# MS20vcf.net
KiCad netlist of a schematic drawn in EAGLE
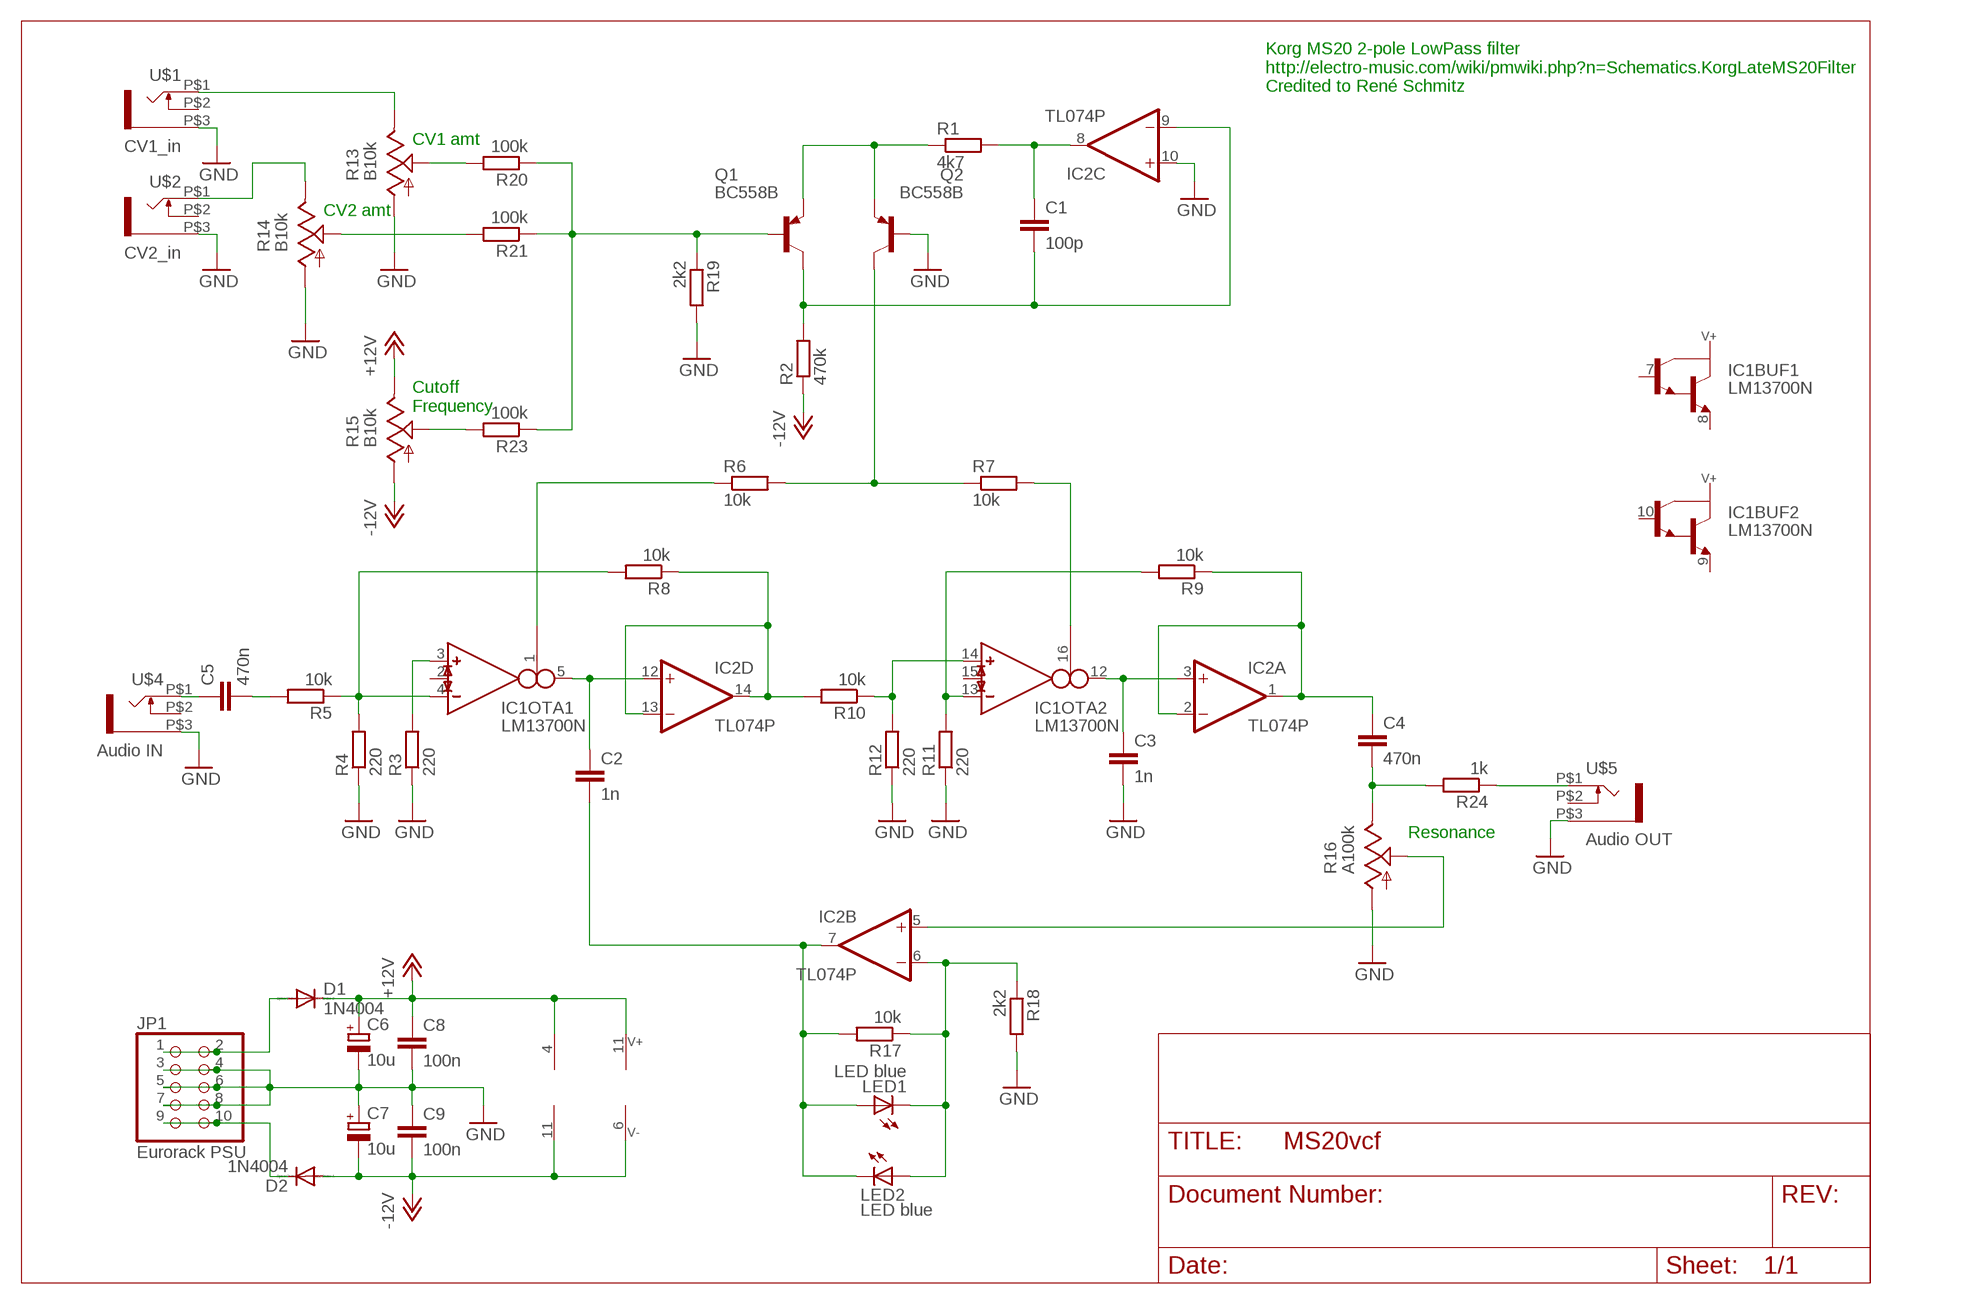
[diagram p0: schematic, sheet 1]

(export (version "E")
  (design (tool "Eeschema 10.0.6"))
  (components
    (comp (ref "C1")
      (value "100p")
      (footprint "eagle-import:C025-025X050")
      (libsource (lib "eagle-import") (part "C-EU025-025X050"))
    )
    (comp (ref "C2")
      (value "1n")
      (footprint "eagle-import:C050-025X075")
      (libsource (lib "eagle-import") (part "C-EU050-025X075"))
    )
    (comp (ref "C3")
      (value "1n")
      (footprint "eagle-import:C050-025X075")
      (libsource (lib "eagle-import") (part "C-EU050-025X075"))
    )
    (comp (ref "C4")
      (value "470n")
      (footprint "eagle-import:C050-025X075")
      (libsource (lib "eagle-import") (part "C-EU050-025X075"))
    )
    (comp (ref "C5")
      (value "470n")
      (footprint "eagle-import:C050-025X075")
      (libsource (lib "eagle-import") (part "C-EU050-025X075"))
    )
    (comp (ref "C6")
      (value "10u")
      (footprint "eagle-import:E2,5-5")
      (libsource (lib "eagle-import") (part "CPOL-EUE2.5-5"))
    )
    (comp (ref "C7")
      (value "10u")
      (footprint "eagle-import:E2,5-5")
      (libsource (lib "eagle-import") (part "CPOL-EUE2.5-5"))
    )
    (comp (ref "C8")
      (value "100n")
      (footprint "eagle-import:C025-025X050")
      (libsource (lib "eagle-import") (part "C-EU025-025X050"))
    )
    (comp (ref "C9")
      (value "100n")
      (footprint "eagle-import:C025-025X050")
      (libsource (lib "eagle-import") (part "C-EU025-025X050"))
    )
    (comp (ref "D1")
      (value "1N4004")
      (footprint "eagle-import:D-7.5")
      (libsource (lib "eagle-import") (part "DIODE-D-7.5"))
    )
    (comp (ref "D2")
      (value "1N4004")
      (footprint "eagle-import:D-7.5")
      (libsource (lib "eagle-import") (part "DIODE-D-7.5"))
    )
    (comp (ref "IC1")
      (value "LM13700N")
      (footprint "eagle-import:DIL16")
      (libsource (lib "eagle-import") (part "LM13700N"))
    )
    (comp (ref "IC2")
      (value "TL074P")
      (footprint "eagle-import:DIL14")
      (libsource (lib "eagle-import") (part "TL074P"))
    )
    (comp (ref "JP1")
      (value "Eurorack PSU")
      (footprint "eagle-import:2X05")
      (libsource (lib "eagle-import") (part "PINHD-2X5"))
    )
    (comp (ref "LED1")
      (value "LED blue")
      (footprint "eagle-import:LED3MM")
      (libsource (lib "eagle-import") (part "LED3MM"))
    )
    (comp (ref "LED2")
      (value "LED blue")
      (footprint "eagle-import:LED3MM")
      (libsource (lib "eagle-import") (part "LED3MM"))
    )
    (comp (ref "Q1")
      (value "BC558B")
      (footprint "eagle-import:TO92-EBC")
      (libsource (lib "eagle-import") (part "BC558C"))
    )
    (comp (ref "Q2")
      (value "BC558B")
      (footprint "eagle-import:TO92-EBC")
      (libsource (lib "eagle-import") (part "BC558C"))
    )
    (comp (ref "R1")
      (value "4k7")
      (footprint "eagle-import:0207_2V")
      (libsource (lib "eagle-import") (part "R-EU_0207/2V"))
    )
    (comp (ref "R2")
      (value "470k")
      (footprint "eagle-import:0207_2V")
      (libsource (lib "eagle-import") (part "R-EU_0207/2V"))
    )
    (comp (ref "R3")
      (value "220")
      (footprint "eagle-import:0207_2V")
      (libsource (lib "eagle-import") (part "R-EU_0207/2V"))
    )
    (comp (ref "R4")
      (value "220")
      (footprint "eagle-import:0207_2V")
      (libsource (lib "eagle-import") (part "R-EU_0207/2V"))
    )
    (comp (ref "R5")
      (value "10k")
      (footprint "eagle-import:0207_2V")
      (libsource (lib "eagle-import") (part "R-EU_0207/2V"))
    )
    (comp (ref "R6")
      (value "10k")
      (footprint "eagle-import:0207_2V")
      (libsource (lib "eagle-import") (part "R-EU_0207/2V"))
    )
    (comp (ref "R7")
      (value "10k")
      (footprint "eagle-import:0207_2V")
      (libsource (lib "eagle-import") (part "R-EU_0207/2V"))
    )
    (comp (ref "R8")
      (value "10k")
      (footprint "eagle-import:0207_2V")
      (libsource (lib "eagle-import") (part "R-EU_0207/2V"))
    )
    (comp (ref "R9")
      (value "10k")
      (footprint "eagle-import:0207_2V")
      (libsource (lib "eagle-import") (part "R-EU_0207/2V"))
    )
    (comp (ref "R10")
      (value "10k")
      (footprint "eagle-import:0207_2V")
      (libsource (lib "eagle-import") (part "R-EU_0207/2V"))
    )
    (comp (ref "R11")
      (value "220")
      (footprint "eagle-import:0207_2V")
      (libsource (lib "eagle-import") (part "R-EU_0207/2V"))
    )
    (comp (ref "R12")
      (value "220")
      (footprint "eagle-import:0207_2V")
      (libsource (lib "eagle-import") (part "R-EU_0207/2V"))
    )
    (comp (ref "R13")
      (value "B10k")
      (footprint "eagle-import:ALPS_POT_VERTICAL")
      (libsource (lib "eagle-import") (part "POT_USVERTICAL"))
    )
    (comp (ref "R14")
      (value "B10k")
      (footprint "eagle-import:ALPS_POT_VERTICAL")
      (libsource (lib "eagle-import") (part "POT_USVERTICAL"))
    )
    (comp (ref "R15")
      (value "B10k")
      (footprint "eagle-import:ALPS_POT_VERTICAL")
      (libsource (lib "eagle-import") (part "POT_USVERTICAL"))
    )
    (comp (ref "R16")
      (value "A100k")
      (footprint "eagle-import:ALPS_POT_VERTICAL")
      (libsource (lib "eagle-import") (part "POT_USVERTICAL"))
    )
    (comp (ref "R17")
      (value "10k")
      (footprint "eagle-import:0207_2V")
      (libsource (lib "eagle-import") (part "R-EU_0207/2V"))
    )
    (comp (ref "R18")
      (value "2k2")
      (footprint "eagle-import:0207_2V")
      (libsource (lib "eagle-import") (part "R-EU_0207/2V"))
    )
    (comp (ref "R19")
      (value "2k2")
      (footprint "eagle-import:0207_2V")
      (libsource (lib "eagle-import") (part "R-EU_0207/2V"))
    )
    (comp (ref "R20")
      (value "100k")
      (footprint "eagle-import:0207_2V")
      (libsource (lib "eagle-import") (part "R-EU_0207/2V"))
    )
    (comp (ref "R21")
      (value "100k")
      (footprint "eagle-import:0207_2V")
      (libsource (lib "eagle-import") (part "R-EU_0207/2V"))
    )
    (comp (ref "R23")
      (value "100k")
      (footprint "eagle-import:0207_2V")
      (libsource (lib "eagle-import") (part "R-EU_0207/2V"))
    )
    (comp (ref "R24")
      (value "1k")
      (footprint "eagle-import:0207_2V")
      (libsource (lib "eagle-import") (part "R-EU_0207/2V"))
    )
    (comp (ref "U$1")
      (value "CV1_in")
      (footprint "eagle-import:WQP-PJ301M-12_JACK")
      (libsource (lib "eagle-import") (part "WQP-PJ301M-12_JACK"))
    )
    (comp (ref "U$2")
      (value "CV2_in")
      (footprint "eagle-import:WQP-PJ301M-12_JACK")
      (libsource (lib "eagle-import") (part "WQP-PJ301M-12_JACK"))
    )
    (comp (ref "U$4")
      (value "Audio IN")
      (footprint "eagle-import:WQP-PJ301M-12_JACK")
      (libsource (lib "eagle-import") (part "WQP-PJ301M-12_JACK"))
    )
    (comp (ref "U$5")
      (value "Audio OUT")
      (footprint "eagle-import:WQP-PJ301M-12_JACK")
      (libsource (lib "eagle-import") (part "WQP-PJ301M-12_JACK"))
    )
  )
  (nets
    (net (code "1") (name "+12V") (class "Default")
      (node (ref "C6") (pin "+") (pinfunction "+_+") (pintype "passive"))
      (node (ref "C8") (pin "1") (pinfunction "1_1") (pintype "passive"))
      (node (ref "D1") (pin "C") (pinfunction "C_C") (pintype "passive"))
      (node (ref "IC1") (pin "11") (pinfunction "V+_11") (pintype "power_in"))
      (node (ref "IC2") (pin "4") (pinfunction "V+_4") (pintype "power_in"))
      (node (ref "R15") (pin "P$1") (pinfunction "E_P$1") (pintype "passive"))
    )
    (net (code "2") (name "-12V") (class "Default")
      (node (ref "C7") (pin "-") (pinfunction "-_-") (pintype "passive"))
      (node (ref "C9") (pin "2") (pinfunction "2_2") (pintype "passive"))
      (node (ref "D2") (pin "A") (pinfunction "A_A") (pintype "passive"))
      (node (ref "IC1") (pin "6") (pinfunction "V-_6") (pintype "power_in"))
      (node (ref "IC2") (pin "11") (pinfunction "V-_11") (pintype "power_in"))
      (node (ref "R15") (pin "P$3") (pinfunction "A_P$3") (pintype "passive"))
      (node (ref "R2") (pin "1") (pinfunction "1_1") (pintype "passive"))
    )
    (net (code "3") (name "GND") (class "Default")
      (node (ref "C3") (pin "2") (pinfunction "2_2") (pintype "passive"))
      (node (ref "C6") (pin "-") (pinfunction "-_-") (pintype "passive"))
      (node (ref "C7") (pin "+") (pinfunction "+_+") (pintype "passive"))
      (node (ref "C8") (pin "2") (pinfunction "2_2") (pintype "passive"))
      (node (ref "C9") (pin "1") (pinfunction "1_1") (pintype "passive"))
      (node (ref "IC2") (pin "10") (pinfunction "+IN_10") (pintype "input"))
      (node (ref "JP1") (pin "3") (pinfunction "3_3") (pintype "passive"))
      (node (ref "JP1") (pin "4") (pinfunction "4_4") (pintype "passive"))
      (node (ref "JP1") (pin "5") (pinfunction "5_5") (pintype "passive"))
      (node (ref "JP1") (pin "6") (pinfunction "6_6") (pintype "passive"))
      (node (ref "JP1") (pin "7") (pinfunction "7_7") (pintype "passive"))
      (node (ref "JP1") (pin "8") (pinfunction "8_8") (pintype "passive"))
      (node (ref "Q2") (pin "B") (pinfunction "B_B") (pintype "passive"))
      (node (ref "R11") (pin "1") (pinfunction "1_1") (pintype "passive"))
      (node (ref "R12") (pin "1") (pinfunction "1_1") (pintype "passive"))
      (node (ref "R13") (pin "P$3") (pinfunction "A_P$3") (pintype "passive"))
      (node (ref "R14") (pin "P$3") (pinfunction "A_P$3") (pintype "passive"))
      (node (ref "R16") (pin "P$3") (pinfunction "A_P$3") (pintype "passive"))
      (node (ref "R18") (pin "2") (pinfunction "2_2") (pintype "passive"))
      (node (ref "R19") (pin "2") (pinfunction "2_2") (pintype "passive"))
      (node (ref "R3") (pin "1") (pinfunction "1_1") (pintype "passive"))
      (node (ref "R4") (pin "1") (pinfunction "1_1") (pintype "passive"))
      (node (ref "U$1") (pin "P$3") (pinfunction "1_P$3") (pintype "passive"))
      (node (ref "U$2") (pin "P$3") (pinfunction "1_P$3") (pintype "passive"))
      (node (ref "U$4") (pin "P$3") (pinfunction "1_P$3") (pintype "passive"))
      (node (ref "U$5") (pin "P$3") (pinfunction "1_P$3") (pintype "passive"))
    )
    (net (code "4") (name "Net-(C5-Pad2)") (class "Default")
      (node (ref "C5") (pin "2") (pinfunction "2_2") (pintype "passive"))
      (node (ref "R5") (pin "2") (pinfunction "2_2") (pintype "passive"))
    )
    (net (code "5") (name "Net-(D1-PadA)") (class "Default")
      (node (ref "D1") (pin "A") (pinfunction "A_A") (pintype "passive"))
      (node (ref "JP1") (pin "1") (pinfunction "1_1") (pintype "passive"))
      (node (ref "JP1") (pin "2") (pinfunction "2_2") (pintype "passive"))
    )
    (net (code "6") (name "Net-(D2-PadC)") (class "Default")
      (node (ref "D2") (pin "C") (pinfunction "C_C") (pintype "passive"))
      (node (ref "JP1") (pin "10") (pinfunction "10_10") (pintype "passive"))
      (node (ref "JP1") (pin "9") (pinfunction "9_9") (pintype "passive"))
    )
    (net (code "7") (name "Net-(IC1C-IN_N)") (class "Default")
      (node (ref "IC1") (pin "4") (pinfunction "IN_N_4") (pintype "input"))
      (node (ref "R4") (pin "2") (pinfunction "2_2") (pintype "passive"))
      (node (ref "R5") (pin "1") (pinfunction "1_1") (pintype "passive"))
      (node (ref "R8") (pin "2") (pinfunction "2_2") (pintype "passive"))
    )
    (net (code "8") (name "Net-(IC1C-IN_P)") (class "Default")
      (node (ref "IC1") (pin "3") (pinfunction "IN_P_3") (pintype "input"))
      (node (ref "R3") (pin "2") (pinfunction "2_2") (pintype "passive"))
    )
    (net (code "9") (name "Net-(IC1C-I_BIAS)") (class "Default")
      (node (ref "IC1") (pin "1") (pinfunction "I_BIAS_1") (pintype "input"))
      (node (ref "R6") (pin "1") (pinfunction "1_1") (pintype "passive"))
    )
    (net (code "10") (name "Net-(IC1C-OUT)") (class "Default")
      (node (ref "C2") (pin "1") (pinfunction "1_1") (pintype "passive"))
      (node (ref "IC1") (pin "5") (pinfunction "OUT_5") (pintype "output"))
      (node (ref "IC2") (pin "12") (pinfunction "+IN_12") (pintype "input"))
    )
    (net (code "11") (name "Net-(IC1D-IN_N)") (class "Default")
      (node (ref "IC1") (pin "13") (pinfunction "IN_N_13") (pintype "input"))
      (node (ref "R11") (pin "2") (pinfunction "2_2") (pintype "passive"))
      (node (ref "R9") (pin "2") (pinfunction "2_2") (pintype "passive"))
    )
    (net (code "12") (name "Net-(IC1D-IN_P)") (class "Default")
      (node (ref "IC1") (pin "14") (pinfunction "IN_P_14") (pintype "input"))
      (node (ref "R10") (pin "1") (pinfunction "1_1") (pintype "passive"))
      (node (ref "R12") (pin "2") (pinfunction "2_2") (pintype "passive"))
    )
    (net (code "13") (name "Net-(IC1D-I_BIAS)") (class "Default")
      (node (ref "IC1") (pin "16") (pinfunction "I_BIAS_16") (pintype "input"))
      (node (ref "R7") (pin "2") (pinfunction "2_2") (pintype "passive"))
    )
    (net (code "14") (name "Net-(IC1D-OUT)") (class "Default")
      (node (ref "C3") (pin "1") (pinfunction "1_1") (pintype "passive"))
      (node (ref "IC1") (pin "12") (pinfunction "OUT_12") (pintype "output"))
      (node (ref "IC2") (pin "3") (pinfunction "+IN_3") (pintype "input"))
    )
    (net (code "15") (name "Net-(IC2A--IN)") (class "Default")
      (node (ref "C4") (pin "1") (pinfunction "1_1") (pintype "passive"))
      (node (ref "IC2") (pin "1") (pinfunction "OUT_1") (pintype "output"))
      (node (ref "IC2") (pin "2") (pinfunction "-IN_2") (pintype "input"))
      (node (ref "R9") (pin "1") (pinfunction "1_1") (pintype "passive"))
    )
    (net (code "16") (name "Net-(IC2B-+IN)") (class "Default")
      (node (ref "IC2") (pin "5") (pinfunction "+IN_5") (pintype "input"))
      (node (ref "R16") (pin "P$2") (pinfunction "S_P$2") (pintype "passive"))
    )
    (net (code "17") (name "Net-(IC2B--IN)") (class "Default")
      (node (ref "IC2") (pin "6") (pinfunction "-IN_6") (pintype "input"))
      (node (ref "LED1") (pin "K") (pinfunction "C_K") (pintype "passive"))
      (node (ref "LED2") (pin "A") (pinfunction "A_A") (pintype "passive"))
      (node (ref "R17") (pin "1") (pinfunction "1_1") (pintype "passive"))
      (node (ref "R18") (pin "1") (pinfunction "1_1") (pintype "passive"))
    )
    (net (code "18") (name "Net-(IC2B-OUT)") (class "Default")
      (node (ref "C2") (pin "2") (pinfunction "2_2") (pintype "passive"))
      (node (ref "IC2") (pin "7") (pinfunction "OUT_7") (pintype "output"))
      (node (ref "LED1") (pin "A") (pinfunction "A_A") (pintype "passive"))
      (node (ref "LED2") (pin "K") (pinfunction "C_K") (pintype "passive"))
      (node (ref "R17") (pin "2") (pinfunction "2_2") (pintype "passive"))
    )
    (net (code "19") (name "Net-(IC2C--IN)") (class "Default")
      (node (ref "C1") (pin "2") (pinfunction "2_2") (pintype "passive"))
      (node (ref "IC2") (pin "9") (pinfunction "-IN_9") (pintype "input"))
      (node (ref "Q1") (pin "C") (pinfunction "C_C") (pintype "passive"))
      (node (ref "R2") (pin "2") (pinfunction "2_2") (pintype "passive"))
    )
    (net (code "20") (name "Net-(IC2C-OUT)") (class "Default")
      (node (ref "C1") (pin "1") (pinfunction "1_1") (pintype "passive"))
      (node (ref "IC2") (pin "8") (pinfunction "OUT_8") (pintype "output"))
      (node (ref "R1") (pin "2") (pinfunction "2_2") (pintype "passive"))
    )
    (net (code "21") (name "Net-(IC2D--IN)") (class "Default")
      (node (ref "IC2") (pin "13") (pinfunction "-IN_13") (pintype "input"))
      (node (ref "IC2") (pin "14") (pinfunction "OUT_14") (pintype "output"))
      (node (ref "R10") (pin "2") (pinfunction "2_2") (pintype "passive"))
      (node (ref "R8") (pin "1") (pinfunction "1_1") (pintype "passive"))
    )
    (net (code "22") (name "Net-(Q1-PadB)") (class "Default")
      (node (ref "Q1") (pin "B") (pinfunction "B_B") (pintype "passive"))
      (node (ref "R19") (pin "1") (pinfunction "1_1") (pintype "passive"))
      (node (ref "R20") (pin "1") (pinfunction "1_1") (pintype "passive"))
      (node (ref "R21") (pin "1") (pinfunction "1_1") (pintype "passive"))
      (node (ref "R23") (pin "1") (pinfunction "1_1") (pintype "passive"))
    )
    (net (code "23") (name "Net-(Q1-PadE)") (class "Default")
      (node (ref "Q1") (pin "E") (pinfunction "E_E") (pintype "passive"))
      (node (ref "Q2") (pin "E") (pinfunction "E_E") (pintype "passive"))
      (node (ref "R1") (pin "1") (pinfunction "1_1") (pintype "passive"))
    )
    (net (code "24") (name "Net-(Q2-PadC)") (class "Default")
      (node (ref "Q2") (pin "C") (pinfunction "C_C") (pintype "passive"))
      (node (ref "R6") (pin "2") (pinfunction "2_2") (pintype "passive"))
      (node (ref "R7") (pin "1") (pinfunction "1_1") (pintype "passive"))
    )
    (net (code "25") (name "Net-(R13-E)") (class "Default")
      (node (ref "R13") (pin "P$1") (pinfunction "E_P$1") (pintype "passive"))
      (node (ref "U$1") (pin "P$1") (pinfunction "2_P$1") (pintype "passive"))
    )
    (net (code "26") (name "Net-(R13-S)") (class "Default")
      (node (ref "R13") (pin "P$2") (pinfunction "S_P$2") (pintype "passive"))
      (node (ref "R20") (pin "2") (pinfunction "2_2") (pintype "passive"))
    )
    (net (code "27") (name "Net-(R14-E)") (class "Default")
      (node (ref "R14") (pin "P$1") (pinfunction "E_P$1") (pintype "passive"))
      (node (ref "U$2") (pin "P$1") (pinfunction "2_P$1") (pintype "passive"))
    )
    (net (code "28") (name "Net-(R14-S)") (class "Default")
      (node (ref "R14") (pin "P$2") (pinfunction "S_P$2") (pintype "passive"))
      (node (ref "R21") (pin "2") (pinfunction "2_2") (pintype "passive"))
    )
    (net (code "29") (name "Net-(R15-S)") (class "Default")
      (node (ref "R15") (pin "P$2") (pinfunction "S_P$2") (pintype "passive"))
      (node (ref "R23") (pin "2") (pinfunction "2_2") (pintype "passive"))
    )
    (net (code "30") (name "Net-(R16-E)") (class "Default")
      (node (ref "C4") (pin "2") (pinfunction "2_2") (pintype "passive"))
      (node (ref "R16") (pin "P$1") (pinfunction "E_P$1") (pintype "passive"))
      (node (ref "R24") (pin "2") (pinfunction "2_2") (pintype "passive"))
    )
    (net (code "31") (name "Net-(U$4-2)") (class "Default")
      (node (ref "C5") (pin "1") (pinfunction "1_1") (pintype "passive"))
      (node (ref "U$4") (pin "P$1") (pinfunction "2_P$1") (pintype "passive"))
    )
    (net (code "32") (name "Net-(U$5-2)") (class "Default")
      (node (ref "R24") (pin "1") (pinfunction "1_1") (pintype "passive"))
      (node (ref "U$5") (pin "P$1") (pinfunction "2_P$1") (pintype "passive"))
    )
    (net (code "33") (name "unconnected-(IC1A-B-Pad7)") (class "Default")
      (node (ref "IC1") (pin "7") (pinfunction "B_7") (pintype "passive"))
    )
    (net (code "34") (name "unconnected-(IC1A-E-Pad8)") (class "Default")
      (node (ref "IC1") (pin "8") (pinfunction "E_8") (pintype "passive"))
    )
    (net (code "35") (name "unconnected-(IC1B-B-Pad10)") (class "Default")
      (node (ref "IC1") (pin "10") (pinfunction "B_10") (pintype "passive"))
    )
    (net (code "36") (name "unconnected-(IC1B-E-Pad9)") (class "Default")
      (node (ref "IC1") (pin "9") (pinfunction "E_9") (pintype "passive"))
    )
    (net (code "37") (name "unconnected-(IC1C-I_DIODE-Pad2)") (class "Default")
      (node (ref "IC1") (pin "2") (pinfunction "I_DIODE_2") (pintype "input"))
    )
    (net (code "38") (name "unconnected-(IC1D-I_DIODE-Pad15)") (class "Default")
      (node (ref "IC1") (pin "15") (pinfunction "I_DIODE_15") (pintype "input"))
    )
    (net (code "39") (name "unconnected-(U$1-3-PadP$2)") (class "Default")
      (node (ref "U$1") (pin "P$2") (pinfunction "3_P$2") (pintype "passive"))
    )
    (net (code "40") (name "unconnected-(U$2-3-PadP$2)") (class "Default")
      (node (ref "U$2") (pin "P$2") (pinfunction "3_P$2") (pintype "passive"))
    )
    (net (code "41") (name "unconnected-(U$4-3-PadP$2)") (class "Default")
      (node (ref "U$4") (pin "P$2") (pinfunction "3_P$2") (pintype "passive"))
    )
    (net (code "42") (name "unconnected-(U$5-3-PadP$2)") (class "Default")
      (node (ref "U$5") (pin "P$2") (pinfunction "3_P$2") (pintype "passive"))
    )
  )
)
